# motherboard.net
KiCad netlist of a schematic drawn in EAGLE
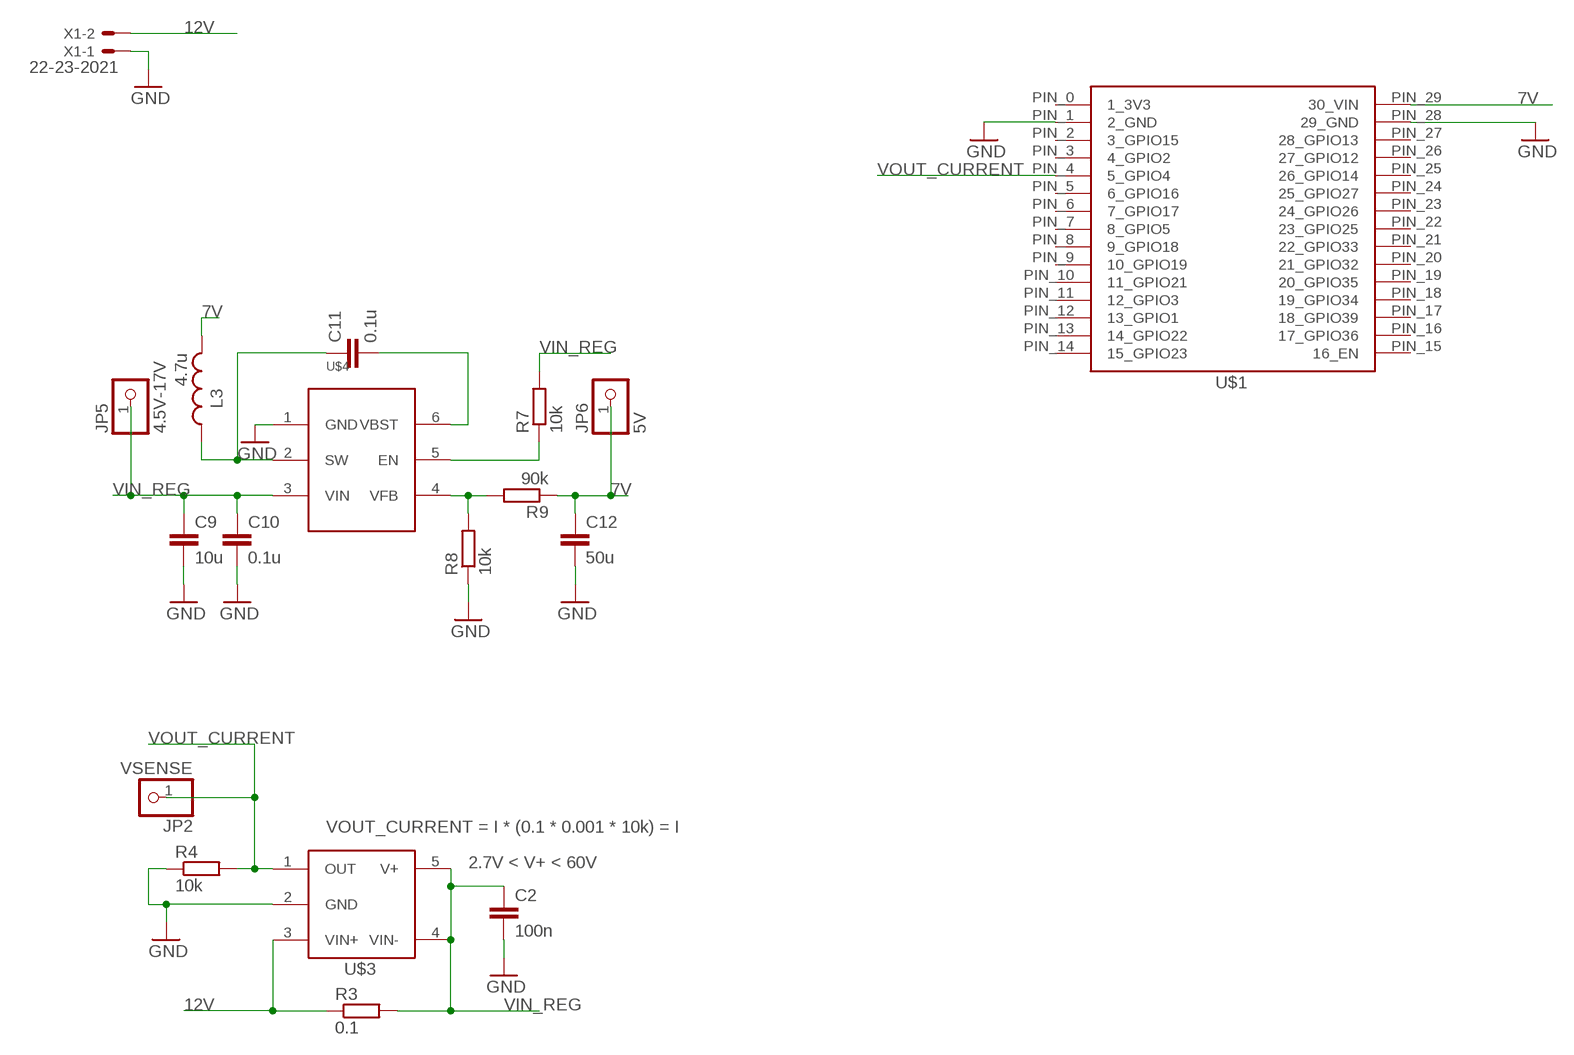
[diagram p0: schematic, sheet 1]

(export (version "E")
  (design (tool "Eeschema 10.0.6"))
  (components
    (comp (ref "C2")
      (value "100n")
      (footprint "eagle-import:C0805")
      (libsource (lib "eagle-import") (part "C-EUC0805"))
    )
    (comp (ref "C9")
      (value "10u")
      (footprint "eagle-import:C0805")
      (libsource (lib "eagle-import") (part "C-EUC0805"))
    )
    (comp (ref "C10")
      (value "0.1u")
      (footprint "eagle-import:C0805")
      (libsource (lib "eagle-import") (part "C-EUC0805"))
    )
    (comp (ref "C11")
      (value "0.1u")
      (footprint "eagle-import:C0805")
      (libsource (lib "eagle-import") (part "C-EUC0805"))
    )
    (comp (ref "C12")
      (value "50u")
      (footprint "eagle-import:C0805")
      (libsource (lib "eagle-import") (part "C-EUC0805"))
    )
    (comp (ref "JP2")
      (value "VSENSE")
      (footprint "eagle-import:1X01")
      (libsource (lib "eagle-import") (part "PINHD-1X1"))
    )
    (comp (ref "JP5")
      (value "4.5V-17V")
      (footprint "eagle-import:1X01")
      (libsource (lib "eagle-import") (part "PINHD-1X1"))
    )
    (comp (ref "JP6")
      (value "5V")
      (footprint "eagle-import:1X01")
      (libsource (lib "eagle-import") (part "PINHD-1X1"))
    )
    (comp (ref "L3")
      (value "4.7u")
      (footprint "eagle-import:L3225M")
      (libsource (lib "eagle-import") (part "L-USL3225M"))
    )
    (comp (ref "R3")
      (value "0.1")
      (footprint "eagle-import:R1206")
      (libsource (lib "eagle-import") (part "R-EU_R1206"))
    )
    (comp (ref "R4")
      (value "10k")
      (footprint "eagle-import:R0805")
      (libsource (lib "eagle-import") (part "R-EU_R0805"))
    )
    (comp (ref "R7")
      (value "10k")
      (footprint "eagle-import:R0805")
      (libsource (lib "eagle-import") (part "R-EU_R0805"))
    )
    (comp (ref "R8")
      (value "10k")
      (footprint "eagle-import:R0805")
      (libsource (lib "eagle-import") (part "R-EU_R0805"))
    )
    (comp (ref "R9")
      (value "90k")
      (footprint "eagle-import:R0805")
      (libsource (lib "eagle-import") (part "R-EU_R0805"))
    )
    (comp (ref "U$1")
      (value "ESP32_DEVKIT_V1")
      (footprint "eagle-import:ESP32_DEVKIT_V1")
      (libsource (lib "eagle-import") (part "ESP32_DEVKIT_V1"))
    )
    (comp (ref "U$3")
      (value "INA169")
      (footprint "eagle-import:SOT23_5_PIN")
      (libsource (lib "eagle-import") (part "INA169"))
    )
    (comp (ref "U$4")
      (value "TPS561201")
      (footprint "eagle-import:SOT23_6_PIN")
      (libsource (lib "eagle-import") (part "TPS561201"))
    )
    (comp (ref "X1")
      (value "22-23-2021")
      (footprint "eagle-import:22-23-2021")
      (fields (field (name "MF") "MOLEX"))
      (libsource (lib "eagle-import") (part "22-23-2021"))
    )
  )
  (nets
    (net (code "1") (name "/7V") (class "Default")
      (node (ref "C12") (pin "1") (pinfunction "1_1") (pintype "passive"))
      (node (ref "JP6") (pin "1") (pinfunction "1_1") (pintype "passive"))
      (node (ref "L3") (pin "2") (pinfunction "2_2") (pintype "passive"))
      (node (ref "R9") (pin "1") (pinfunction "1_1") (pintype "passive"))
      (node (ref "U$1") (pin "PIN_29") (pinfunction "30_VIN_PIN_29") (pintype "bidirectional"))
    )
    (net (code "2") (name "/12V") (class "Default")
      (node (ref "R3") (pin "1") (pinfunction "1_1") (pintype "passive"))
      (node (ref "U$3") (pin "3") (pinfunction "VIN+_3") (pintype "bidirectional"))
      (node (ref "X1") (pin "2") (pinfunction "S_2") (pintype "passive"))
    )
    (net (code "3") (name "/VIN_REG") (class "Default")
      (node (ref "C10") (pin "1") (pinfunction "1_1") (pintype "passive"))
      (node (ref "C2") (pin "1") (pinfunction "1_1") (pintype "passive"))
      (node (ref "C9") (pin "1") (pinfunction "1_1") (pintype "passive"))
      (node (ref "JP5") (pin "1") (pinfunction "1_1") (pintype "passive"))
      (node (ref "R3") (pin "2") (pinfunction "2_2") (pintype "passive"))
      (node (ref "R7") (pin "2") (pinfunction "2_2") (pintype "passive"))
      (node (ref "U$3") (pin "4") (pinfunction "VIN-_4") (pintype "bidirectional"))
      (node (ref "U$3") (pin "5") (pinfunction "V+_5") (pintype "bidirectional"))
      (node (ref "U$4") (pin "3") (pinfunction "VIN_3") (pintype "bidirectional"))
    )
    (net (code "4") (name "/VOUT_CURRENT") (class "Default")
      (node (ref "JP2") (pin "1") (pinfunction "1_1") (pintype "passive"))
      (node (ref "R4") (pin "2") (pinfunction "2_2") (pintype "passive"))
      (node (ref "U$1") (pin "PIN_4") (pinfunction "5_GPIO4_PIN_4") (pintype "bidirectional"))
      (node (ref "U$3") (pin "1") (pinfunction "OUT_1") (pintype "bidirectional"))
    )
    (net (code "5") (name "GND") (class "Default")
      (node (ref "C10") (pin "2") (pinfunction "2_2") (pintype "passive"))
      (node (ref "C12") (pin "2") (pinfunction "2_2") (pintype "passive"))
      (node (ref "C2") (pin "2") (pinfunction "2_2") (pintype "passive"))
      (node (ref "C9") (pin "2") (pinfunction "2_2") (pintype "passive"))
      (node (ref "R4") (pin "1") (pinfunction "1_1") (pintype "passive"))
      (node (ref "R8") (pin "1") (pinfunction "1_1") (pintype "passive"))
      (node (ref "U$1") (pin "PIN_1") (pinfunction "2_GND_PIN_1") (pintype "bidirectional"))
      (node (ref "U$1") (pin "PIN_28") (pinfunction "29_GND_PIN_28") (pintype "bidirectional"))
      (node (ref "U$3") (pin "2") (pinfunction "GND_2") (pintype "bidirectional"))
      (node (ref "U$4") (pin "1") (pinfunction "GND_1") (pintype "bidirectional"))
      (node (ref "X1") (pin "1") (pinfunction "S_1") (pintype "passive"))
    )
    (net (code "6") (name "Net-(U$4-EN)") (class "Default")
      (node (ref "R7") (pin "1") (pinfunction "1_1") (pintype "passive"))
      (node (ref "U$4") (pin "5") (pinfunction "EN_5") (pintype "bidirectional"))
    )
    (net (code "7") (name "Net-(U$4-SW)") (class "Default")
      (node (ref "C11") (pin "1") (pinfunction "1_1") (pintype "passive"))
      (node (ref "L3") (pin "1") (pinfunction "1_1") (pintype "passive"))
      (node (ref "U$4") (pin "2") (pinfunction "SW_2") (pintype "bidirectional"))
    )
    (net (code "8") (name "Net-(U$4-VBST)") (class "Default")
      (node (ref "C11") (pin "2") (pinfunction "2_2") (pintype "passive"))
      (node (ref "U$4") (pin "6") (pinfunction "VBST_6") (pintype "bidirectional"))
    )
    (net (code "9") (name "Net-(U$4-VFB)") (class "Default")
      (node (ref "R8") (pin "2") (pinfunction "2_2") (pintype "passive"))
      (node (ref "R9") (pin "2") (pinfunction "2_2") (pintype "passive"))
      (node (ref "U$4") (pin "4") (pinfunction "VFB_4") (pintype "bidirectional"))
    )
    (net (code "10") (name "unconnected-(U$1-1_3V3-PadPIN_0)") (class "Default")
      (node (ref "U$1") (pin "PIN_0") (pinfunction "1_3V3_PIN_0") (pintype "bidirectional"))
    )
    (net (code "11") (name "unconnected-(U$1-3_GPIO15-PadPIN_2)") (class "Default")
      (node (ref "U$1") (pin "PIN_2") (pinfunction "3_GPIO15_PIN_2") (pintype "bidirectional"))
    )
    (net (code "12") (name "unconnected-(U$1-4_GPIO2-PadPIN_3)") (class "Default")
      (node (ref "U$1") (pin "PIN_3") (pinfunction "4_GPIO2_PIN_3") (pintype "bidirectional"))
    )
    (net (code "13") (name "unconnected-(U$1-6_GPIO16-PadPIN_5)") (class "Default")
      (node (ref "U$1") (pin "PIN_5") (pinfunction "6_GPIO16_PIN_5") (pintype "bidirectional"))
    )
    (net (code "14") (name "unconnected-(U$1-7_GPIO17-PadPIN_6)") (class "Default")
      (node (ref "U$1") (pin "PIN_6") (pinfunction "7_GPIO17_PIN_6") (pintype "bidirectional"))
    )
    (net (code "15") (name "unconnected-(U$1-8_GPIO5-PadPIN_7)") (class "Default")
      (node (ref "U$1") (pin "PIN_7") (pinfunction "8_GPIO5_PIN_7") (pintype "bidirectional"))
    )
    (net (code "16") (name "unconnected-(U$1-9_GPIO18-PadPIN_8)") (class "Default")
      (node (ref "U$1") (pin "PIN_8") (pinfunction "9_GPIO18_PIN_8") (pintype "bidirectional"))
    )
    (net (code "17") (name "unconnected-(U$1-10_GPIO19-PadPIN_9)") (class "Default")
      (node (ref "U$1") (pin "PIN_9") (pinfunction "10_GPIO19_PIN_9") (pintype "bidirectional"))
    )
    (net (code "18") (name "unconnected-(U$1-11_GPIO21-PadPIN_10)") (class "Default")
      (node (ref "U$1") (pin "PIN_10") (pinfunction "11_GPIO21_PIN_10") (pintype "bidirectional"))
    )
    (net (code "19") (name "unconnected-(U$1-12_GPIO3-PadPIN_11)") (class "Default")
      (node (ref "U$1") (pin "PIN_11") (pinfunction "12_GPIO3_PIN_11") (pintype "bidirectional"))
    )
    (net (code "20") (name "unconnected-(U$1-13_GPIO1-PadPIN_12)") (class "Default")
      (node (ref "U$1") (pin "PIN_12") (pinfunction "13_GPIO1_PIN_12") (pintype "bidirectional"))
    )
    (net (code "21") (name "unconnected-(U$1-14_GPIO22-PadPIN_13)") (class "Default")
      (node (ref "U$1") (pin "PIN_13") (pinfunction "14_GPIO22_PIN_13") (pintype "bidirectional"))
    )
    (net (code "22") (name "unconnected-(U$1-15_GPIO23-PadPIN_14)") (class "Default")
      (node (ref "U$1") (pin "PIN_14") (pinfunction "15_GPIO23_PIN_14") (pintype "bidirectional"))
    )
    (net (code "23") (name "unconnected-(U$1-16_EN-PadPIN_15)") (class "Default")
      (node (ref "U$1") (pin "PIN_15") (pinfunction "16_EN_PIN_15") (pintype "bidirectional"))
    )
    (net (code "24") (name "unconnected-(U$1-17_GPIO36-PadPIN_16)") (class "Default")
      (node (ref "U$1") (pin "PIN_16") (pinfunction "17_GPIO36_PIN_16") (pintype "bidirectional"))
    )
    (net (code "25") (name "unconnected-(U$1-18_GPIO39-PadPIN_17)") (class "Default")
      (node (ref "U$1") (pin "PIN_17") (pinfunction "18_GPIO39_PIN_17") (pintype "bidirectional"))
    )
    (net (code "26") (name "unconnected-(U$1-19_GPIO34-PadPIN_18)") (class "Default")
      (node (ref "U$1") (pin "PIN_18") (pinfunction "19_GPIO34_PIN_18") (pintype "bidirectional"))
    )
    (net (code "27") (name "unconnected-(U$1-20_GPIO35-PadPIN_19)") (class "Default")
      (node (ref "U$1") (pin "PIN_19") (pinfunction "20_GPIO35_PIN_19") (pintype "bidirectional"))
    )
    (net (code "28") (name "unconnected-(U$1-21_GPIO32-PadPIN_20)") (class "Default")
      (node (ref "U$1") (pin "PIN_20") (pinfunction "21_GPIO32_PIN_20") (pintype "bidirectional"))
    )
    (net (code "29") (name "unconnected-(U$1-22_GPIO33-PadPIN_21)") (class "Default")
      (node (ref "U$1") (pin "PIN_21") (pinfunction "22_GPIO33_PIN_21") (pintype "bidirectional"))
    )
    (net (code "30") (name "unconnected-(U$1-23_GPIO25-PadPIN_22)") (class "Default")
      (node (ref "U$1") (pin "PIN_22") (pinfunction "23_GPIO25_PIN_22") (pintype "bidirectional"))
    )
    (net (code "31") (name "unconnected-(U$1-24_GPIO26-PadPIN_23)") (class "Default")
      (node (ref "U$1") (pin "PIN_23") (pinfunction "24_GPIO26_PIN_23") (pintype "bidirectional"))
    )
    (net (code "32") (name "unconnected-(U$1-25_GPIO27-PadPIN_24)") (class "Default")
      (node (ref "U$1") (pin "PIN_24") (pinfunction "25_GPIO27_PIN_24") (pintype "bidirectional"))
    )
    (net (code "33") (name "unconnected-(U$1-26_GPIO14-PadPIN_25)") (class "Default")
      (node (ref "U$1") (pin "PIN_25") (pinfunction "26_GPIO14_PIN_25") (pintype "bidirectional"))
    )
    (net (code "34") (name "unconnected-(U$1-27_GPIO12-PadPIN_26)") (class "Default")
      (node (ref "U$1") (pin "PIN_26") (pinfunction "27_GPIO12_PIN_26") (pintype "bidirectional"))
    )
    (net (code "35") (name "unconnected-(U$1-28_GPIO13-PadPIN_27)") (class "Default")
      (node (ref "U$1") (pin "PIN_27") (pinfunction "28_GPIO13_PIN_27") (pintype "bidirectional"))
    )
  )
)
